# 5_External_MCU_Connections.net
KiCad netlist of a schematic drawn in Altium Designer
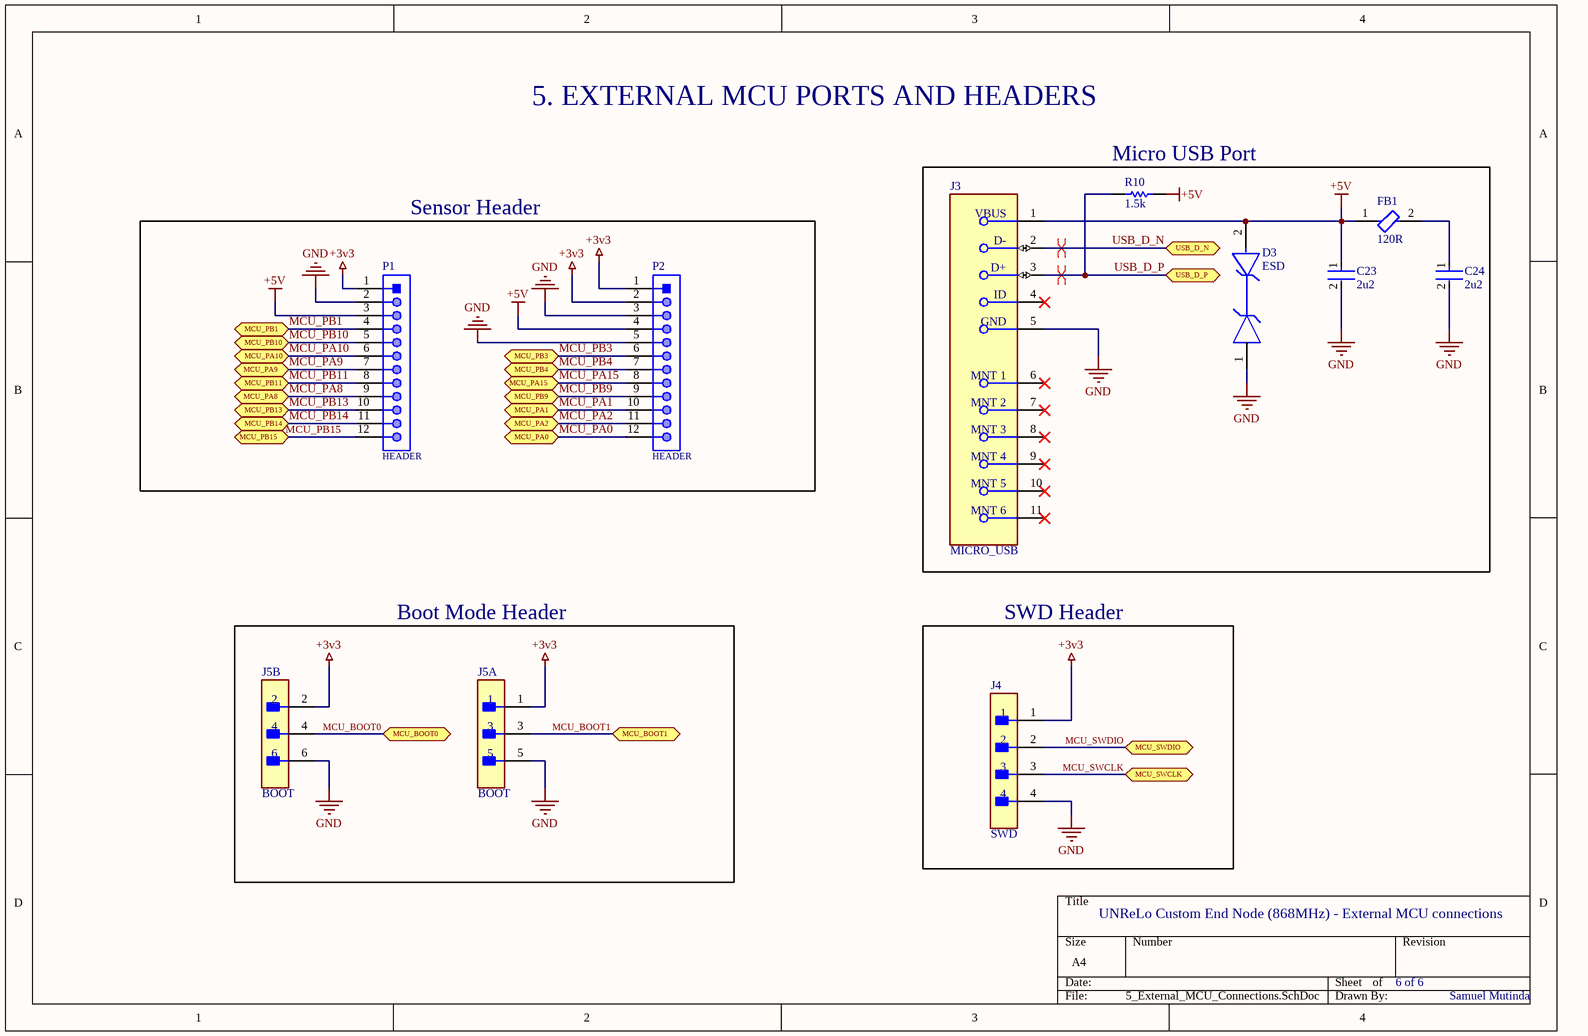
[diagram p0: 5_External_MCU_Connections.SchDoc]

(export (version "E")
  (design (tool "Eeschema 10.0.6"))
  (components
    (comp (ref "C23")
      (value "2u2")
      (footprint "FP-C0603C225K4PACTU-MFG")
      (description "CAP CER 2.2UF 16V X5R 0603")
      (fields (field (name "TOLERANCE") "10%") (field (name "VOLTAGE") "16V"))
      (libsource (lib "Altium Content Vault") (part "b4654b650e69147ec39a6b967a45e02"))
    )
    (comp (ref "C24")
      (value "2u2")
      (footprint "FP-C0603C225K4PACTU-MFG")
      (description "CAP CER 2.2UF 16V X5R 0603")
      (fields (field (name "TOLERANCE") "10%") (field (name "VOLTAGE") "16V"))
      (libsource (lib "Altium Content Vault") (part "b4654b650e69147ec39a6b967a45e02"))
    )
    (comp (ref "D3")
      (value "ESD")
      (footprint "FP-711AM-CA-MFG")
      (description "TVS DIODE 5.3V 2XDFN")
      (fields (field (name "OCTOPART") "https://octopart.com/szesd7471n2t5g-on+semiconductor-47358903"))
      (libsource (lib "Altium Content Vault") (part "0b9db586c93572e573b6553f432f587"))
    )
    (comp (ref "FB1")
      (value "120R")
      (footprint "FP-MMZ1005-IPC_B")
      (description "Signal Line Ferrite Bead 120Ω @ 100MHz 500mA DCR 220mΩ SMD 0402")
      (fields (field (name "TOLERANCE") "25%"))
      (libsource (lib "Altium Content Vault") (part "5f30dd21d616792df468990f7003faa"))
    )
    (comp (ref "J3")
      (value "MICRO_USB")
      (footprint "FP-473460001-MFG")
      (description "CONN RCPT USB2.0 MICRO B SMD R/A")
      (fields (field (name "OCTOPART") "https://octopart.com/47346-0001-molex-7164928"))
      (libsource (lib "Altium Content Vault") (part "53ae1f1d9b557310b43ca686e5bb76a"))
    )
    (comp (ref "J4")
      (value "SWD")
      (footprint "FP-47053-1000-MFG")
      (description "CONN HEADER VERT 4POS 2.54MM")
      (libsource (lib "Altium Content Vault") (part "299a8cea1bdcbc3624fe62c390fa72c"))
    )
    (comp (ref "J5")
      (value "BOOT")
      (footprint "FP-M20-9980346-MFG")
      (description "CONN HEADER VERT 6POS 2.54MM")
      (fields
        (field (name "MANUFACTURER PART NUMBER") "M20-9980346")
        (field (name "MANUFACTURER") "Harwin")
        (field (name "OCTOPART") "https://octopart.com/m20-9980346-harwin-5436545")
      )
      (libsource (lib "Altium Content Vault") (part "2654a11fb13586ecb194516b1c997bc"))
    )
    (comp (ref "P1")
      (value "HEADER")
      (footprint "61301211121")
      (description "THT Vertical Pin Header WR-PHD, Pitch 2.54 mm, Single Row, 12 pins")
      (fields (field (name "PUBLISHER") "WurthElektronik"))
      (libsource (lib "Altium Content Vault") (part "WE-CN-1P-M-R12"))
    )
    (comp (ref "P2")
      (value "HEADER")
      (footprint "61301211121")
      (description "THT Vertical Pin Header WR-PHD, Pitch 2.54 mm, Single Row, 12 pins")
      (fields (field (name "PUBLISHER") "WurthElektronik"))
      (libsource (lib "Altium Content Vault") (part "WE-CN-1P-M-R12"))
    )
    (comp (ref "R10")
      (value "1.5k")
      (footprint "RESC1005X40X25ML05T10")
      (fields (field (name "MANUFACTURER") "Yageo / Phycomp") (field (name "PART NUMBER") "RC0402FR-071K5L"))
      (libsource (lib "Altium Content Vault") (part "RES"))
    )
  )
  (nets
    (net (code "1") (name "+3v3") (class "Default")
      (node (ref "J4") (pin "1") (pinfunction "1_1") (pintype "passive"))
      (node (ref "J5") (pin "1") (pinfunction "1_1") (pintype "passive"))
      (node (ref "J5") (pin "2") (pinfunction "2_2") (pintype "passive"))
      (node (ref "P1") (pin "1") (pinfunction "1_1") (pintype "passive"))
      (node (ref "P2") (pin "1") (pinfunction "1_1") (pintype "passive"))
      (node (ref "P2") (pin "2") (pinfunction "2_2") (pintype "passive"))
    )
    (net (code "2") (name "+5V") (class "Default")
      (node (ref "C23") (pin "1") (pinfunction "1_1") (pintype "passive"))
      (node (ref "D3") (pin "2") (pinfunction "2_2") (pintype "passive"))
      (node (ref "FB1") (pin "1") (pinfunction "1_1") (pintype "passive"))
      (node (ref "J3") (pin "1") (pinfunction "VBUS_1") (pintype "power_in"))
      (node (ref "P1") (pin "3") (pinfunction "3_3") (pintype "passive"))
      (node (ref "P2") (pin "4") (pinfunction "4_4") (pintype "passive"))
      (node (ref "R10") (pin "2") (pinfunction "2_2") (pintype "passive"))
    )
    (net (code "3") (name "/MCU_BOOT0") (class "Default")
      (node (ref "J5") (pin "4") (pinfunction "4_4") (pintype "passive"))
    )
    (net (code "4") (name "/MCU_BOOT1") (class "Default")
      (node (ref "J5") (pin "3") (pinfunction "3_3") (pintype "passive"))
    )
    (net (code "5") (name "/MCU_PA0") (class "Default")
      (node (ref "P2") (pin "12") (pinfunction "12_12") (pintype "passive"))
    )
    (net (code "6") (name "/MCU_PA1") (class "Default")
      (node (ref "P2") (pin "10") (pinfunction "10_10") (pintype "passive"))
    )
    (net (code "7") (name "/MCU_PA2") (class "Default")
      (node (ref "P2") (pin "11") (pinfunction "11_11") (pintype "passive"))
    )
    (net (code "8") (name "/MCU_PA8") (class "Default")
      (node (ref "P1") (pin "9") (pinfunction "9_9") (pintype "passive"))
    )
    (net (code "9") (name "/MCU_PA9") (class "Default")
      (node (ref "P1") (pin "7") (pinfunction "7_7") (pintype "passive"))
    )
    (net (code "10") (name "/MCU_PA10") (class "Default")
      (node (ref "P1") (pin "6") (pinfunction "6_6") (pintype "passive"))
    )
    (net (code "11") (name "/MCU_PA15") (class "Default")
      (node (ref "P2") (pin "8") (pinfunction "8_8") (pintype "passive"))
    )
    (net (code "12") (name "/MCU_PB1") (class "Default")
      (node (ref "P1") (pin "4") (pinfunction "4_4") (pintype "passive"))
    )
    (net (code "13") (name "/MCU_PB3") (class "Default")
      (node (ref "P2") (pin "6") (pinfunction "6_6") (pintype "passive"))
    )
    (net (code "14") (name "/MCU_PB4") (class "Default")
      (node (ref "P2") (pin "7") (pinfunction "7_7") (pintype "passive"))
    )
    (net (code "15") (name "/MCU_PB9") (class "Default")
      (node (ref "P2") (pin "9") (pinfunction "9_9") (pintype "passive"))
    )
    (net (code "16") (name "/MCU_PB10") (class "Default")
      (node (ref "P1") (pin "5") (pinfunction "5_5") (pintype "passive"))
    )
    (net (code "17") (name "/MCU_PB11") (class "Default")
      (node (ref "P1") (pin "8") (pinfunction "8_8") (pintype "passive"))
    )
    (net (code "18") (name "/MCU_PB13") (class "Default")
      (node (ref "P1") (pin "10") (pinfunction "10_10") (pintype "passive"))
    )
    (net (code "19") (name "/MCU_PB14") (class "Default")
      (node (ref "P1") (pin "11") (pinfunction "11_11") (pintype "passive"))
    )
    (net (code "20") (name "/MCU_PB15") (class "Default")
      (node (ref "P1") (pin "12") (pinfunction "12_12") (pintype "passive"))
    )
    (net (code "21") (name "/MCU_SWCLK") (class "Default")
      (node (ref "J4") (pin "3") (pinfunction "3_3") (pintype "passive"))
    )
    (net (code "22") (name "/MCU_SWDIO") (class "Default")
      (node (ref "J4") (pin "2") (pinfunction "2_2") (pintype "passive"))
    )
    (net (code "23") (name "/USB_D_N") (class "Default")
      (node (ref "J3") (pin "2") (pinfunction "D-_2") (pintype "bidirectional"))
    )
    (net (code "24") (name "/USB_D_P") (class "Default")
      (node (ref "J3") (pin "3") (pinfunction "D+_3") (pintype "bidirectional"))
      (node (ref "R10") (pin "1") (pinfunction "1_1") (pintype "passive"))
    )
    (net (code "25") (name "GND") (class "Default")
      (node (ref "C23") (pin "2") (pinfunction "2_2") (pintype "passive"))
      (node (ref "C24") (pin "2") (pinfunction "2_2") (pintype "passive"))
      (node (ref "D3") (pin "1") (pinfunction "1_1") (pintype "passive"))
      (node (ref "J3") (pin "5") (pinfunction "GND_5") (pintype "power_in"))
      (node (ref "J4") (pin "4") (pinfunction "4_4") (pintype "passive"))
      (node (ref "J5") (pin "5") (pinfunction "5_5") (pintype "passive"))
      (node (ref "J5") (pin "6") (pinfunction "6_6") (pintype "passive"))
      (node (ref "P1") (pin "2") (pinfunction "2_2") (pintype "passive"))
      (node (ref "P2") (pin "3") (pinfunction "3_3") (pintype "passive"))
      (node (ref "P2") (pin "5") (pinfunction "5_5") (pintype "passive"))
    )
    (net (code "26") (name "Net-(C24-Pad1)") (class "Default")
      (node (ref "C24") (pin "1") (pinfunction "1_1") (pintype "passive"))
      (node (ref "FB1") (pin "2") (pinfunction "2_2") (pintype "passive"))
    )
    (net (code "27") (name "unconnected-(J3-ID-Pad4)") (class "Default")
      (node (ref "J3") (pin "4") (pinfunction "ID_4") (pintype "passive+no_connect"))
    )
    (net (code "28") (name "unconnected-(J3-MNT_1-Pad6)") (class "Default")
      (node (ref "J3") (pin "6") (pinfunction "MNT_1_6") (pintype "passive+no_connect"))
    )
    (net (code "29") (name "unconnected-(J3-MNT_2-Pad7)") (class "Default")
      (node (ref "J3") (pin "7") (pinfunction "MNT_2_7") (pintype "passive+no_connect"))
    )
    (net (code "30") (name "unconnected-(J3-MNT_3-Pad8)") (class "Default")
      (node (ref "J3") (pin "8") (pinfunction "MNT_3_8") (pintype "passive+no_connect"))
    )
    (net (code "31") (name "unconnected-(J3-MNT_4-Pad9)") (class "Default")
      (node (ref "J3") (pin "9") (pinfunction "MNT_4_9") (pintype "passive+no_connect"))
    )
    (net (code "32") (name "unconnected-(J3-MNT_5-Pad10)") (class "Default")
      (node (ref "J3") (pin "10") (pinfunction "MNT_5_10") (pintype "passive+no_connect"))
    )
    (net (code "33") (name "unconnected-(J3-MNT_6-Pad11)") (class "Default")
      (node (ref "J3") (pin "11") (pinfunction "MNT_6_11") (pintype "passive+no_connect"))
    )
  )
)
